# Tailsitter_sch.net
KiCad netlist of a schematic drawn in Altium Designer
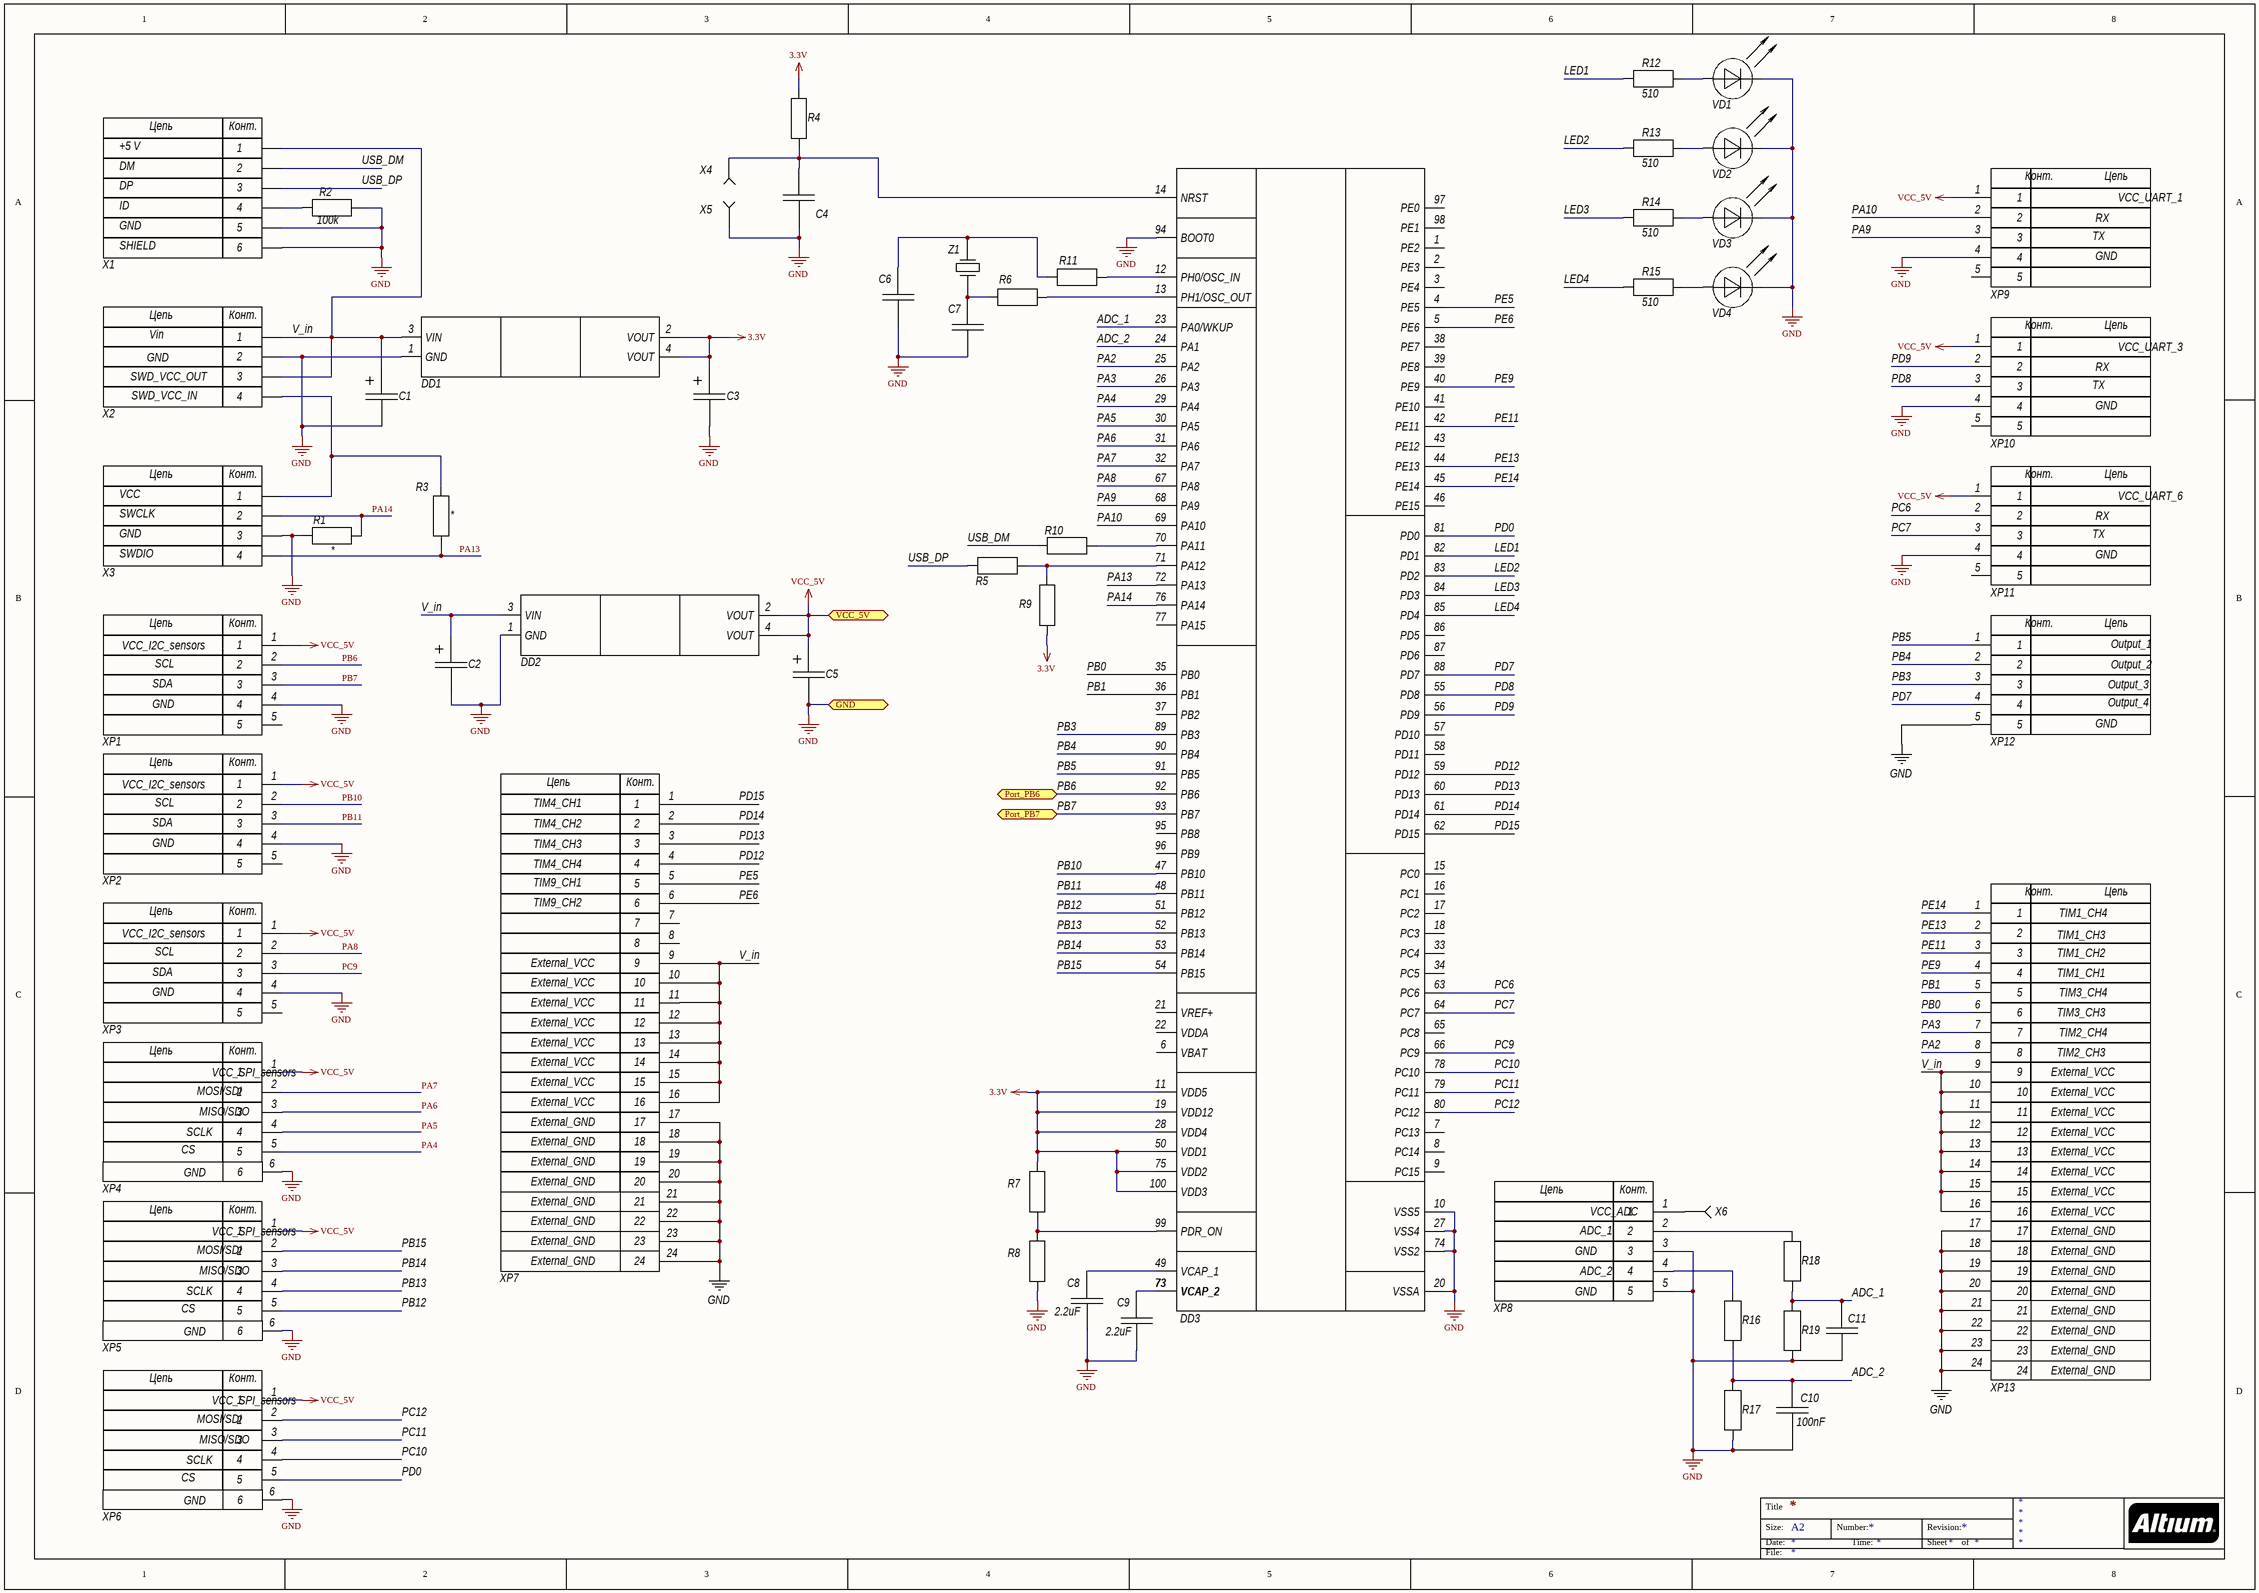
[diagram p0: Tailsitter_sch.SchDoc]

(export (version "E")
  (design (tool "Eeschema 10.0.6"))
  (components
    (comp (ref "C1")
      (value "Cap El Case A (Tantalum)")
      (footprint "CAP CASE A")
      (libsource (lib "Capacitors") (part "Cap El Case A (Tantalum)"))
    )
    (comp (ref "C2")
      (value "Cap El Case A (Tantalum)")
      (footprint "CAP CASE A")
      (libsource (lib "Capacitors") (part "Cap El Case A (Tantalum)"))
    )
    (comp (ref "C3")
      (value "Cap El Case A (Tantalum)")
      (footprint "CAP CASE A")
      (libsource (lib "Capacitors") (part "Cap El Case A (Tantalum)"))
    )
    (comp (ref "C4")
      (value "Cap EIA 0805")
      (footprint "CAP EIA 0805")
      (libsource (lib "Capacitors") (part "Cap EIA 0805"))
    )
    (comp (ref "C5")
      (value "Cap El Case A (Tantalum)")
      (footprint "CAP CASE A")
      (libsource (lib "Capacitors") (part "Cap El Case A (Tantalum)"))
    )
    (comp (ref "C6")
      (value "Cap EIA 0805")
      (footprint "CAP EIA 0805")
      (libsource (lib "Capacitors") (part "Cap EIA 0805"))
    )
    (comp (ref "C7")
      (value "Cap EIA 0805")
      (footprint "CAP EIA 0805")
      (libsource (lib "Capacitors") (part "Cap EIA 0805"))
    )
    (comp (ref "C8")
      (value "2.2uF")
      (footprint "CAP EIA 0805")
      (fields (field (name "Comment") "Cap EIA 0805"))
      (libsource (lib "Capacitors") (part "Cap EIA 0805"))
    )
    (comp (ref "C9")
      (value "2.2uF")
      (footprint "CAP EIA 0805")
      (fields (field (name "Comment") "Cap EIA 0805"))
      (libsource (lib "Capacitors") (part "Cap EIA 0805"))
    )
    (comp (ref "C10")
      (value "100nF")
      (footprint "CAP EIA 0805")
      (fields (field (name "Comment") "Cap EIA 0805"))
      (libsource (lib "Capacitors") (part "Cap EIA 0805"))
    )
    (comp (ref "C11")
      (value "Cap EIA 0805")
      (footprint "CAP EIA 0805")
      (libsource (lib "Capacitors") (part "Cap EIA 0805"))
    )
    (comp (ref "DD1")
      (value "LM1117S50")
      (footprint "SOT-223_M")
      (description "LDO Voltage Regulator")
      (fields (field (name "MANUFACTURER") "ST Microelectronics"))
      (libsource (lib "Integrated_Circuits") (part "LM1117S50"))
    )
    (comp (ref "DD2")
      (value "LM1117S50")
      (footprint "SOT-223_M")
      (description "LDO Voltage Regulator")
      (fields (field (name "MANUFACTURER") "ST Microelectronics"))
      (libsource (lib "Integrated_Circuits") (part "LM1117S50"))
    )
    (comp (ref "DD3")
      (value "STM32F407")
      (footprint "LQFP 14x14-100L")
      (description "ARM Cortex-M4 MCU with 1 Mbytes Flash, 168 MHz CPU")
      (fields (field (name "MANUFACTURER") "ST"))
      (libsource (lib "Integrated_Circuits") (part "STM32F407"))
    )
    (comp (ref "R1")
      (value "*")
      (footprint "RES EIA 0805")
      (fields (field (name "ALTIUM_VALUE") "*"))
      (libsource (lib "Resistors") (part "Res EIA 0805"))
    )
    (comp (ref "R2")
      (value "100k")
      (footprint "RES EIA 0805")
      (fields (field (name "Comment") "Res EIA 0805"))
      (libsource (lib "Resistors") (part "Res EIA 0805"))
    )
    (comp (ref "R3")
      (value "*")
      (footprint "RES EIA 0805")
      (fields (field (name "ALTIUM_VALUE") "*"))
      (libsource (lib "Resistors") (part "Res EIA 0805"))
    )
    (comp (ref "R4")
      (value "Res EIA 0805")
      (footprint "RES EIA 0805")
      (libsource (lib "Resistors") (part "Res EIA 0805"))
    )
    (comp (ref "R5")
      (value "Res EIA 0805")
      (footprint "RES EIA 0805")
      (libsource (lib "Resistors") (part "Res EIA 0805"))
    )
    (comp (ref "R6")
      (value "Res EIA 0805")
      (footprint "RES EIA 0805")
      (libsource (lib "Resistors") (part "Res EIA 0805"))
    )
    (comp (ref "R7")
      (value "Res EIA 0805")
      (footprint "RES EIA 0805")
      (libsource (lib "Resistors") (part "Res EIA 0805"))
    )
    (comp (ref "R8")
      (value "Res EIA 0805")
      (footprint "RES EIA 0805")
      (libsource (lib "Resistors") (part "Res EIA 0805"))
    )
    (comp (ref "R9")
      (value "Res EIA 0805")
      (footprint "RES EIA 0805")
      (libsource (lib "Resistors") (part "Res EIA 0805"))
    )
    (comp (ref "R10")
      (value "Res EIA 0805")
      (footprint "RES EIA 0805")
      (libsource (lib "Resistors") (part "Res EIA 0805"))
    )
    (comp (ref "R11")
      (value "Res EIA 0805")
      (footprint "RES EIA 0805")
      (libsource (lib "Resistors") (part "Res EIA 0805"))
    )
    (comp (ref "R12")
      (value "510")
      (footprint "RES EIA 0805")
      (fields (field (name "Comment") "Res EIA 0805"))
      (libsource (lib "Resistors") (part "Res EIA 0805"))
    )
    (comp (ref "R13")
      (value "510")
      (footprint "RES EIA 0805")
      (fields (field (name "Comment") "Res EIA 0805"))
      (libsource (lib "Resistors") (part "Res EIA 0805"))
    )
    (comp (ref "R14")
      (value "510")
      (footprint "RES EIA 0805")
      (fields (field (name "Comment") "Res EIA 0805"))
      (libsource (lib "Resistors") (part "Res EIA 0805"))
    )
    (comp (ref "R15")
      (value "510")
      (footprint "RES EIA 0805")
      (fields (field (name "Comment") "Res EIA 0805"))
      (libsource (lib "Resistors") (part "Res EIA 0805"))
    )
    (comp (ref "R16")
      (value "Res EIA 0805")
      (footprint "RES EIA 0805")
      (libsource (lib "Resistors") (part "Res EIA 0805"))
    )
    (comp (ref "R17")
      (value "Res EIA 0805")
      (footprint "RES EIA 0805")
      (libsource (lib "Resistors") (part "Res EIA 0805"))
    )
    (comp (ref "R18")
      (value "Res EIA 0805")
      (footprint "RES EIA 0805")
      (libsource (lib "Resistors") (part "Res EIA 0805"))
    )
    (comp (ref "R19")
      (value "Res EIA 0805")
      (footprint "RES EIA 0805")
      (libsource (lib "Resistors") (part "Res EIA 0805"))
    )
    (comp (ref "VD1")
      (value "KP-2012xxxx")
      (footprint "SMD LED 0805 (GREEN)")
      (description "SMD Led")
      (libsource (lib "Semiconductors") (part "FYLS-0805xxxx"))
    )
    (comp (ref "VD2")
      (value "KP-2012xxxx")
      (footprint "SMD LED 0805 (GREEN)")
      (description "SMD Led")
      (libsource (lib "Semiconductors") (part "FYLS-0805xxxx"))
    )
    (comp (ref "VD3")
      (value "KP-2012xxxx")
      (footprint "SMD LED 0805 (GREEN)")
      (description "SMD Led")
      (libsource (lib "Semiconductors") (part "FYLS-0805xxxx"))
    )
    (comp (ref "VD4")
      (value "KP-2012xxxx")
      (footprint "SMD LED 0805 (GREEN)")
      (description "SMD Led")
      (libsource (lib "Semiconductors") (part "FYLS-0805xxxx"))
    )
    (comp (ref "X1")
      (value "USB/M-1J")
      (footprint "USB/M-1J (DS1104)")
      (description "Mini USB Receptacle")
      (fields (field (name "MANUFACTURER") "Connfly"))
      (libsource (lib "Connectors") (part "USB/M-1J"))
    )
    (comp (ref "X2")
      (value "~")
      (footprint "SWD")
      (fields (field (name "MANUFACTURER") "Hsuan Mao(Китай)"))
      (libsource (lib "Connectors") (part "PLS-4"))
    )
    (comp (ref "X3")
      (value "~")
      (footprint "SWD")
      (fields (field (name "MANUFACTURER") "Тайвань(Китай)"))
      (libsource (lib "Connectors") (part "SWD(PLS- 4)"))
    )
    (comp (ref "X4")
      (value "Pin_Referal")
      (footprint "Pin - Referal")
      (description "Generic Pin Contact")
      (libsource (lib "Connectors") (part "Pin_Referal"))
    )
    (comp (ref "X5")
      (value "Pin_Referal")
      (footprint "Pin - Referal")
      (description "Generic Pin Contact")
      (libsource (lib "Connectors") (part "Pin_Referal"))
    )
    (comp (ref "X6")
      (value "Pin_Referal")
      (footprint "Pin - Referal")
      (description "Generic Pin Contact")
      (libsource (lib "Connectors") (part "Pin_Referal"))
    )
    (comp (ref "XP1")
      (value "BM05B-SRSS-TB")
      (footprint "BM05B-SRSS-TB")
      (description "5-Pin Angle Connector")
      (fields (field (name "MANUFACTURER") "JST"))
      (libsource (lib "Connectors") (part "BM05B-SRSS-TB"))
    )
    (comp (ref "XP2")
      (value "BM05B-SRSS-TB")
      (footprint "BM05B-SRSS-TB")
      (description "5-Pin Angle Connector")
      (fields (field (name "MANUFACTURER") "JST"))
      (libsource (lib "Connectors") (part "BM05B-SRSS-TB"))
    )
    (comp (ref "XP3")
      (value "BM05B-SRSS-TB")
      (footprint "BM05B-SRSS-TB")
      (description "5-Pin Angle Connector")
      (fields (field (name "MANUFACTURER") "JST"))
      (libsource (lib "Connectors") (part "BM05B-SRSS-TB"))
    )
    (comp (ref "XP4")
      (value "Micro JST 6 pin")
      (footprint "Micro JST-6 pin")
      (libsource (lib "Connectors") (part "Micro JST-6 pin"))
    )
    (comp (ref "XP5")
      (value "Micro JST 6 pin")
      (footprint "Micro JST-6 pin")
      (libsource (lib "Connectors") (part "Micro JST-6 pin"))
    )
    (comp (ref "XP6")
      (value "Micro JST 6 pin")
      (footprint "Micro JST-6 pin")
      (libsource (lib "Connectors") (part "Micro JST-6 pin"))
    )
    (comp (ref "XP7")
      (value "PLD-24-3")
      (footprint "PLD-24-3")
      (description "Разъем для подключение RC-приемника или регуляторов хода")
      (libsource (lib "Connectors") (part "PLD-24-3"))
    )
    (comp (ref "XP8")
      (value "BM05B-SRSS-TB")
      (footprint "BM05B-SRSS-TB")
      (description "5-Pin Angle Connector")
      (fields (field (name "MANUFACTURER") "JST"))
      (libsource (lib "Connectors") (part "BM05B-SRSS-TB"))
    )
    (comp (ref "XP9")
      (value "BM05B-SRSS-TB")
      (footprint "BM05B-SRSS-TB")
      (description "5-Pin Angle Connector")
      (fields (field (name "MANUFACTURER") "JST"))
      (libsource (lib "Connectors") (part "BM05B-SRSS-TB"))
    )
    (comp (ref "XP10")
      (value "BM05B-SRSS-TB")
      (footprint "BM05B-SRSS-TB")
      (description "5-Pin Angle Connector")
      (fields (field (name "MANUFACTURER") "JST"))
      (libsource (lib "Connectors") (part "BM05B-SRSS-TB"))
    )
    (comp (ref "XP11")
      (value "BM05B-SRSS-TB")
      (footprint "BM05B-SRSS-TB")
      (description "5-Pin Angle Connector")
      (fields (field (name "MANUFACTURER") "JST"))
      (libsource (lib "Connectors") (part "BM05B-SRSS-TB"))
    )
    (comp (ref "XP12")
      (value "BM05B-SRSS-TB")
      (footprint "BM05B-SRSS-TB")
      (description "5-Pin Angle Connector")
      (fields (field (name "MANUFACTURER") "JST"))
      (libsource (lib "Connectors") (part "BM05B-SRSS-TB"))
    )
    (comp (ref "XP13")
      (value "PLD-24-3")
      (footprint "PLD-24-3")
      (description "Разъем для подключение RC-приемника или регуляторов хода")
      (libsource (lib "Connectors") (part "PLD-24-3"))
    )
    (comp (ref "Z1")
      (value "ABM3-8.000MHZ-D2Y-T")
      (footprint "bq smd 5x3.2")
      (fields (field (name "MANUFACTURER") "ABRACON"))
      (libsource (lib "Converters") (part "ABM3-8.000MHZ-D2Y-T"))
    )
  )
  (nets
    (net (code "1") (name "/ADC_1") (class "Default")
      (node (ref "C11") (pin "1") (pinfunction "1_1") (pintype "passive"))
      (node (ref "DD3") (pin "23") (pinfunction "PA0/WKUP_23") (pintype "passive"))
      (node (ref "R18") (pin "1") (pinfunction "1_1") (pintype "passive"))
      (node (ref "R19") (pin "2") (pinfunction "2_2") (pintype "passive"))
    )
    (net (code "2") (name "/ADC_2") (class "Default")
      (node (ref "C10") (pin "1") (pinfunction "1_1") (pintype "passive"))
      (node (ref "DD3") (pin "24") (pinfunction "PA1_24") (pintype "passive"))
      (node (ref "R16") (pin "1") (pinfunction "1_1") (pintype "passive"))
      (node (ref "R17") (pin "2") (pinfunction "2_2") (pintype "passive"))
    )
    (net (code "3") (name "/LED1") (class "Default")
      (node (ref "DD3") (pin "82") (pinfunction "PD1_82") (pintype "passive"))
      (node (ref "R12") (pin "1") (pinfunction "1_1") (pintype "passive"))
    )
    (net (code "4") (name "/LED2") (class "Default")
      (node (ref "DD3") (pin "83") (pinfunction "PD2_83") (pintype "passive"))
      (node (ref "R13") (pin "1") (pinfunction "1_1") (pintype "passive"))
    )
    (net (code "5") (name "/LED3") (class "Default")
      (node (ref "DD3") (pin "84") (pinfunction "PD3_84") (pintype "passive"))
      (node (ref "R14") (pin "1") (pinfunction "1_1") (pintype "passive"))
    )
    (net (code "6") (name "/LED4") (class "Default")
      (node (ref "DD3") (pin "85") (pinfunction "PD4_85") (pintype "passive"))
      (node (ref "R15") (pin "1") (pinfunction "1_1") (pintype "passive"))
    )
    (net (code "7") (name "/PA2") (class "Default")
      (node (ref "DD3") (pin "25") (pinfunction "PA2_25") (pintype "passive"))
      (node (ref "XP13") (pin "8") (pinfunction "8_8") (pintype "passive"))
    )
    (net (code "8") (name "/PA3") (class "Default")
      (node (ref "DD3") (pin "26") (pinfunction "PA3_26") (pintype "passive"))
      (node (ref "XP13") (pin "7") (pinfunction "7_7") (pintype "passive"))
    )
    (net (code "9") (name "/PA4") (class "Default")
      (node (ref "DD3") (pin "29") (pinfunction "PA4_29") (pintype "passive"))
      (node (ref "XP4") (pin "5") (pinfunction "5_5") (pintype "passive"))
    )
    (net (code "10") (name "/PA5") (class "Default")
      (node (ref "DD3") (pin "30") (pinfunction "PA5_30") (pintype "passive"))
      (node (ref "XP4") (pin "4") (pinfunction "4_4") (pintype "passive"))
    )
    (net (code "11") (name "/PA6") (class "Default")
      (node (ref "DD3") (pin "31") (pinfunction "PA6_31") (pintype "passive"))
      (node (ref "XP4") (pin "3") (pinfunction "3_3") (pintype "passive"))
    )
    (net (code "12") (name "/PA7") (class "Default")
      (node (ref "DD3") (pin "32") (pinfunction "PA7_32") (pintype "passive"))
      (node (ref "XP4") (pin "2") (pinfunction "2_2") (pintype "passive"))
    )
    (net (code "13") (name "/PA8") (class "Default")
      (node (ref "DD3") (pin "67") (pinfunction "PA8_67") (pintype "passive"))
      (node (ref "XP3") (pin "2") (pinfunction "2_2") (pintype "passive"))
    )
    (net (code "14") (name "/PA9") (class "Default")
      (node (ref "DD3") (pin "68") (pinfunction "PA9_68") (pintype "passive"))
      (node (ref "XP9") (pin "3") (pinfunction "3_3") (pintype "passive"))
    )
    (net (code "15") (name "/PA10") (class "Default")
      (node (ref "DD3") (pin "69") (pinfunction "PA10_69") (pintype "passive"))
      (node (ref "XP9") (pin "2") (pinfunction "2_2") (pintype "passive"))
    )
    (net (code "16") (name "/PA13") (class "Default")
      (node (ref "DD3") (pin "72") (pinfunction "PA13_72") (pintype "passive"))
      (node (ref "R3") (pin "2") (pinfunction "2_2") (pintype "passive"))
      (node (ref "X3") (pin "4") (pinfunction "SWDIO_4") (pintype "passive"))
    )
    (net (code "17") (name "/PA14") (class "Default")
      (node (ref "DD3") (pin "76") (pinfunction "PA14_76") (pintype "passive"))
      (node (ref "R1") (pin "1") (pinfunction "1_1") (pintype "passive"))
      (node (ref "X3") (pin "2") (pinfunction "SWCLK_2") (pintype "passive"))
    )
    (net (code "18") (name "/PB0") (class "Default")
      (node (ref "DD3") (pin "35") (pinfunction "PB0_35") (pintype "passive"))
      (node (ref "XP13") (pin "6") (pinfunction "6_6") (pintype "passive"))
    )
    (net (code "19") (name "/PB1") (class "Default")
      (node (ref "DD3") (pin "36") (pinfunction "PB1_36") (pintype "passive"))
      (node (ref "XP13") (pin "5") (pinfunction "5_5") (pintype "passive"))
    )
    (net (code "20") (name "/PB3") (class "Default")
      (node (ref "DD3") (pin "89") (pinfunction "PB3_89") (pintype "passive"))
      (node (ref "XP12") (pin "3") (pinfunction "3_3") (pintype "passive"))
    )
    (net (code "21") (name "/PB4") (class "Default")
      (node (ref "DD3") (pin "90") (pinfunction "PB4_90") (pintype "passive"))
      (node (ref "XP12") (pin "2") (pinfunction "2_2") (pintype "passive"))
    )
    (net (code "22") (name "/PB5") (class "Default")
      (node (ref "DD3") (pin "91") (pinfunction "PB5_91") (pintype "passive"))
      (node (ref "XP12") (pin "1") (pinfunction "1_1") (pintype "passive"))
    )
    (net (code "23") (name "/PB6") (class "Default")
      (node (ref "DD3") (pin "92") (pinfunction "PB6_92") (pintype "passive"))
      (node (ref "XP1") (pin "2") (pinfunction "2_2") (pintype "passive"))
    )
    (net (code "24") (name "/PB7") (class "Default")
      (node (ref "DD3") (pin "93") (pinfunction "PB7_93") (pintype "passive"))
      (node (ref "XP1") (pin "3") (pinfunction "3_3") (pintype "passive"))
    )
    (net (code "25") (name "/PB10") (class "Default")
      (node (ref "DD3") (pin "47") (pinfunction "PB10_47") (pintype "passive"))
      (node (ref "XP2") (pin "2") (pinfunction "2_2") (pintype "passive"))
    )
    (net (code "26") (name "/PB11") (class "Default")
      (node (ref "DD3") (pin "48") (pinfunction "PB11_48") (pintype "passive"))
      (node (ref "XP2") (pin "3") (pinfunction "3_3") (pintype "passive"))
    )
    (net (code "27") (name "/PB12") (class "Default")
      (node (ref "DD3") (pin "51") (pinfunction "PB12_51") (pintype "passive"))
      (node (ref "XP5") (pin "5") (pinfunction "5_5") (pintype "passive"))
    )
    (net (code "28") (name "/PB13") (class "Default")
      (node (ref "DD3") (pin "52") (pinfunction "PB13_52") (pintype "passive"))
      (node (ref "XP5") (pin "4") (pinfunction "4_4") (pintype "passive"))
    )
    (net (code "29") (name "/PB14") (class "Default")
      (node (ref "DD3") (pin "53") (pinfunction "PB14_53") (pintype "passive"))
      (node (ref "XP5") (pin "3") (pinfunction "3_3") (pintype "passive"))
    )
    (net (code "30") (name "/PB15") (class "Default")
      (node (ref "DD3") (pin "54") (pinfunction "PB15_54") (pintype "passive"))
      (node (ref "XP5") (pin "2") (pinfunction "2_2") (pintype "passive"))
    )
    (net (code "31") (name "/PC6") (class "Default")
      (node (ref "DD3") (pin "63") (pinfunction "PC6_63") (pintype "passive"))
      (node (ref "XP11") (pin "2") (pinfunction "2_2") (pintype "passive"))
    )
    (net (code "32") (name "/PC7") (class "Default")
      (node (ref "DD3") (pin "64") (pinfunction "PC7_64") (pintype "passive"))
      (node (ref "XP11") (pin "3") (pinfunction "3_3") (pintype "passive"))
    )
    (net (code "33") (name "/PC9") (class "Default")
      (node (ref "DD3") (pin "66") (pinfunction "PC9_66") (pintype "passive"))
      (node (ref "XP3") (pin "3") (pinfunction "3_3") (pintype "passive"))
    )
    (net (code "34") (name "/PC10") (class "Default")
      (node (ref "DD3") (pin "78") (pinfunction "PC10_78") (pintype "passive"))
      (node (ref "XP6") (pin "4") (pinfunction "4_4") (pintype "passive"))
    )
    (net (code "35") (name "/PC11") (class "Default")
      (node (ref "DD3") (pin "79") (pinfunction "PC11_79") (pintype "passive"))
      (node (ref "XP6") (pin "3") (pinfunction "3_3") (pintype "passive"))
    )
    (net (code "36") (name "/PC12") (class "Default")
      (node (ref "DD3") (pin "80") (pinfunction "PC12_80") (pintype "passive"))
      (node (ref "XP6") (pin "2") (pinfunction "2_2") (pintype "passive"))
    )
    (net (code "37") (name "/PD0") (class "Default")
      (node (ref "DD3") (pin "81") (pinfunction "PD0_81") (pintype "passive"))
      (node (ref "XP6") (pin "5") (pinfunction "5_5") (pintype "passive"))
    )
    (net (code "38") (name "/PD7") (class "Default")
      (node (ref "DD3") (pin "88") (pinfunction "PD7_88") (pintype "passive"))
      (node (ref "XP12") (pin "4") (pinfunction "4_4") (pintype "passive"))
    )
    (net (code "39") (name "/PD8") (class "Default")
      (node (ref "DD3") (pin "55") (pinfunction "PD8_55") (pintype "passive"))
      (node (ref "XP10") (pin "3") (pinfunction "3_3") (pintype "passive"))
    )
    (net (code "40") (name "/PD9") (class "Default")
      (node (ref "DD3") (pin "56") (pinfunction "PD9_56") (pintype "passive"))
      (node (ref "XP10") (pin "2") (pinfunction "2_2") (pintype "passive"))
    )
    (net (code "41") (name "/PD12") (class "Default")
      (node (ref "DD3") (pin "59") (pinfunction "PD12_59") (pintype "passive"))
      (node (ref "XP7") (pin "4") (pinfunction "4_4") (pintype "passive"))
    )
    (net (code "42") (name "/PD13") (class "Default")
      (node (ref "DD3") (pin "60") (pinfunction "PD13_60") (pintype "passive"))
      (node (ref "XP7") (pin "3") (pinfunction "3_3") (pintype "passive"))
    )
    (net (code "43") (name "/PD14") (class "Default")
      (node (ref "DD3") (pin "61") (pinfunction "PD14_61") (pintype "passive"))
      (node (ref "XP7") (pin "2") (pinfunction "2_2") (pintype "passive"))
    )
    (net (code "44") (name "/PD15") (class "Default")
      (node (ref "DD3") (pin "62") (pinfunction "PD15_62") (pintype "passive"))
      (node (ref "XP7") (pin "1") (pinfunction "1_1") (pintype "passive"))
    )
    (net (code "45") (name "/PE5") (class "Default")
      (node (ref "DD3") (pin "4") (pinfunction "PE5_4") (pintype "passive"))
      (node (ref "XP7") (pin "5") (pinfunction "5_5") (pintype "passive"))
    )
    (net (code "46") (name "/PE6") (class "Default")
      (node (ref "DD3") (pin "5") (pinfunction "PE6_5") (pintype "passive"))
      (node (ref "XP7") (pin "6") (pinfunction "6_6") (pintype "passive"))
    )
    (net (code "47") (name "/PE9") (class "Default")
      (node (ref "DD3") (pin "40") (pinfunction "PE9_40") (pintype "passive"))
      (node (ref "XP13") (pin "4") (pinfunction "4_4") (pintype "passive"))
    )
    (net (code "48") (name "/PE11") (class "Default")
      (node (ref "DD3") (pin "42") (pinfunction "PE11_42") (pintype "passive"))
      (node (ref "XP13") (pin "3") (pinfunction "3_3") (pintype "passive"))
    )
    (net (code "49") (name "/PE13") (class "Default")
      (node (ref "DD3") (pin "44") (pinfunction "PE13_44") (pintype "passive"))
      (node (ref "XP13") (pin "2") (pinfunction "2_2") (pintype "passive"))
    )
    (net (code "50") (name "/PE14") (class "Default")
      (node (ref "DD3") (pin "45") (pinfunction "PE14_45") (pintype "passive"))
      (node (ref "XP13") (pin "1") (pinfunction "1_1") (pintype "passive"))
    )
    (net (code "51") (name "/USB_DM") (class "Default")
      (node (ref "R10") (pin "1") (pinfunction "1_1") (pintype "passive"))
      (node (ref "X1") (pin "2") (pinfunction "DM_2") (pintype "passive"))
    )
    (net (code "52") (name "/USB_DP") (class "Default")
      (node (ref "R5") (pin "1") (pinfunction "1_1") (pintype "passive"))
      (node (ref "X1") (pin "3") (pinfunction "DP_3") (pintype "passive"))
    )
    (net (code "53") (name "/V_in") (class "Default")
      (node (ref "C1") (pin "1") (pinfunction "1_1") (pintype "passive"))
      (node (ref "C2") (pin "1") (pinfunction "1_1") (pintype "passive"))
      (node (ref "DD1") (pin "3") (pinfunction "VIN_3") (pintype "passive"))
      (node (ref "DD2") (pin "3") (pinfunction "VIN_3") (pintype "passive"))
      (node (ref "X1") (pin "1") (pinfunction "+5_V_1") (pintype "passive"))
      (node (ref "X2") (pin "1") (pinfunction "1_1") (pintype "passive"))
      (node (ref "X2") (pin "3") (pinfunction "3_3") (pintype "passive"))
      (node (ref "XP13") (pin "10") (pinfunction "10_10") (pintype "passive"))
      (node (ref "XP13") (pin "11") (pinfunction "11_11") (pintype "passive"))
      (node (ref "XP13") (pin "12") (pinfunction "12_12") (pintype "passive"))
      (node (ref "XP13") (pin "13") (pinfunction "13_13") (pintype "passive"))
      (node (ref "XP13") (pin "14") (pinfunction "14_14") (pintype "passive"))
      (node (ref "XP13") (pin "15") (pinfunction "15_15") (pintype "passive"))
      (node (ref "XP13") (pin "16") (pinfunction "16_16") (pintype "passive"))
      (node (ref "XP13") (pin "9") (pinfunction "9_9") (pintype "passive"))
      (node (ref "XP7") (pin "10") (pinfunction "10_10") (pintype "passive"))
      (node (ref "XP7") (pin "11") (pinfunction "11_11") (pintype "passive"))
      (node (ref "XP7") (pin "12") (pinfunction "12_12") (pintype "passive"))
      (node (ref "XP7") (pin "13") (pinfunction "13_13") (pintype "passive"))
      (node (ref "XP7") (pin "14") (pinfunction "14_14") (pintype "passive"))
      (node (ref "XP7") (pin "15") (pinfunction "15_15") (pintype "passive"))
      (node (ref "XP7") (pin "16") (pinfunction "16_16") (pintype "passive"))
      (node (ref "XP7") (pin "9") (pinfunction "9_9") (pintype "passive"))
    )
    (net (code "54") (name "3.3V") (class "Default")
      (node (ref "C3") (pin "1") (pinfunction "1_1") (pintype "passive"))
      (node (ref "DD1") (pin "2") (pinfunction "VOUT_2") (pintype "passive"))
      (node (ref "DD1") (pin "4") (pinfunction "VOUT_4") (pintype "passive"))
      (node (ref "DD3") (pin "100") (pinfunction "VDD3_100") (pintype "passive"))
      (node (ref "DD3") (pin "11") (pinfunction "VDD5_11") (pintype "passive"))
      (node (ref "DD3") (pin "19") (pinfunction "VDD12_19") (pintype "passive"))
      (node (ref "DD3") (pin "28") (pinfunction "VDD4_28") (pintype "passive"))
      (node (ref "DD3") (pin "50") (pinfunction "VDD1_50") (pintype "passive"))
      (node (ref "DD3") (pin "75") (pinfunction "VDD2_75") (pintype "passive"))
      (node (ref "R4") (pin "2") (pinfunction "2_2") (pintype "passive"))
      (node (ref "R7") (pin "2") (pinfunction "2_2") (pintype "passive"))
      (node (ref "R9") (pin "1") (pinfunction "1_1") (pintype "passive"))
    )
    (net (code "55") (name "GND") (class "Default")
      (node (ref "C1") (pin "2") (pinfunction "2_2") (pintype "passive"))
      (node (ref "C10") (pin "2") (pinfunction "2_2") (pintype "passive"))
      (node (ref "C11") (pin "2") (pinfunction "2_2") (pintype "passive"))
      (node (ref "C2") (pin "2") (pinfunction "2_2") (pintype "passive"))
      (node (ref "C3") (pin "2") (pinfunction "2_2") (pintype "passive"))
      (node (ref "C4") (pin "1") (pinfunction "1_1") (pintype "passive"))
      (node (ref "C5") (pin "2") (pinfunction "2_2") (pintype "passive"))
      (node (ref "C6") (pin "2") (pinfunction "2_2") (pintype "passive"))
      (node (ref "C7") (pin "2") (pinfunction "2_2") (pintype "passive"))
      (node (ref "C8") (pin "1") (pinfunction "1_1") (pintype "passive"))
      (node (ref "C9") (pin "1") (pinfunction "1_1") (pintype "passive"))
      (node (ref "DD1") (pin "1") (pinfunction "GND_1") (pintype "passive"))
      (node (ref "DD2") (pin "1") (pinfunction "GND_1") (pintype "passive"))
      (node (ref "DD3") (pin "10") (pinfunction "VSS5_10") (pintype "passive"))
      (node (ref "DD3") (pin "20") (pinfunction "VSSA_20") (pintype "passive"))
      (node (ref "DD3") (pin "27") (pinfunction "VSS4_27") (pintype "passive"))
      (node (ref "DD3") (pin "74") (pinfunction "VSS2_74") (pintype "passive"))
      (node (ref "DD3") (pin "94") (pinfunction "BOOT0_94") (pintype "passive"))
      (node (ref "R1") (pin "2") (pinfunction "2_2") (pintype "passive"))
      (node (ref "R17") (pin "1") (pinfunction "1_1") (pintype "passive"))
      (node (ref "R19") (pin "1") (pinfunction "1_1") (pintype "passive"))
      (node (ref "R2") (pin "2") (pinfunction "2_2") (pintype "passive"))
      (node (ref "R8") (pin "2") (pinfunction "2_2") (pintype "passive"))
      (node (ref "VD1") (pin "2") (pinfunction "K_2") (pintype "passive"))
      (node (ref "VD2") (pin "2") (pinfunction "K_2") (pintype "passive"))
      (node (ref "VD3") (pin "2") (pinfunction "K_2") (pintype "passive"))
      (node (ref "VD4") (pin "2") (pinfunction "K_2") (pintype "passive"))
      (node (ref "X1") (pin "5") (pinfunction "GND_5") (pintype "passive"))
      (node (ref "X2") (pin "2") (pinfunction "2_2") (pintype "passive"))
      (node (ref "X3") (pin "3") (pinfunction "GND_3") (pintype "passive"))
      (node (ref "X5") (pin "1") (pinfunction "1_1") (pintype "passive"))
      (node (ref "XP1") (pin "4") (pinfunction "4_4") (pintype "passive"))
      (node (ref "XP10") (pin "4") (pinfunction "4_4") (pintype "passive"))
      (node (ref "XP11") (pin "4") (pinfunction "4_4") (pintype "passive"))
      (node (ref "XP12") (pin "5") (pinfunction "5_5") (pintype "passive"))
      (node (ref "XP13") (pin "17") (pinfunction "17_17") (pintype "passive"))
      (node (ref "XP13") (pin "18") (pinfunction "18_18") (pintype "passive"))
      (node (ref "XP13") (pin "19") (pinfunction "19_19") (pintype "passive"))
      (node (ref "XP13") (pin "20") (pinfunction "20_20") (pintype "passive"))
      (node (ref "XP13") (pin "21") (pinfunction "21_21") (pintype "passive"))
      (node (ref "XP13") (pin "22") (pinfunction "22_22") (pintype "passive"))
      (node (ref "XP13") (pin "23") (pinfunction "23_23") (pintype "passive"))
      (node (ref "XP13") (pin "24") (pinfunction "24_24") (pintype "passive"))
      (node (ref "XP2") (pin "4") (pinfunction "4_4") (pintype "passive"))
      (node (ref "XP3") (pin "4") (pinfunction "4_4") (pintype "passive"))
      (node (ref "XP4") (pin "6") (pinfunction "6_6") (pintype "passive"))
      (node (ref "XP5") (pin "6") (pinfunction "6_6") (pintype "passive"))
      (node (ref "XP6") (pin "6") (pinfunction "6_6") (pintype "passive"))
      (node (ref "XP7") (pin "17") (pinfunction "17_17") (pintype "passive"))
      (node (ref "XP7") (pin "18") (pinfunction "18_18") (pintype "passive"))
      (node (ref "XP7") (pin "19") (pinfunction "19_19") (pintype "passive"))
      (node (ref "XP7") (pin "20") (pinfunction "20_20") (pintype "passive"))
      (node (ref "XP7") (pin "21") (pinfunction "21_21") (pintype "passive"))
      (node (ref "XP7") (pin "22") (pinfunction "22_22") (pintype "passive"))
      (node (ref "XP7") (pin "23") (pinfunction "23_23") (pintype "passive"))
      (node (ref "XP7") (pin "24") (pinfunction "24_24") (pintype "passive"))
      (node (ref "XP8") (pin "3") (pinfunction "3_3") (pintype "passive"))
      (node (ref "XP8") (pin "5") (pinfunction "5_5") (pintype "passive"))
      (node (ref "XP9") (pin "4") (pinfunction "4_4") (pintype "passive"))
    )
    (net (code "56") (name "Net-(C6-Pad1)") (class "Default")
      (node (ref "C6") (pin "1") (pinfunction "1_1") (pintype "passive"))
      (node (ref "R11") (pin "1") (pinfunction "1_1") (pintype "passive"))
      (node (ref "Z1") (pin "1") (pinfunction "1_1") (pintype "passive"))
    )
    (net (code "57") (name "Net-(C7-Pad1)") (class "Default")
      (node (ref "C7") (pin "1") (pinfunction "1_1") (pintype "passive"))
      (node (ref "R6") (pin "1") (pinfunction "1_1") (pintype "passive"))
      (node (ref "Z1") (pin "2") (pinfunction "2_2") (pintype "passive"))
    )
    (net (code "58") (name "Net-(DD3-NRST)") (class "Default")
      (node (ref "C4") (pin "2") (pinfunction "2_2") (pintype "passive"))
      (node (ref "DD3") (pin "14") (pinfunction "NRST_14") (pintype "passive"))
      (node (ref "R4") (pin "1") (pinfunction "1_1") (pintype "passive"))
      (node (ref "X4") (pin "1") (pinfunction "1_1") (pintype "passive"))
    )
    (net (code "59") (name "Net-(DD3-PA11)") (class "Default")
      (node (ref "DD3") (pin "70") (pinfunction "PA11_70") (pintype "passive"))
      (node (ref "R10") (pin "2") (pinfunction "2_2") (pintype "passive"))
    )
    (net (code "60") (name "Net-(DD3-PA12)") (class "Default")
      (node (ref "DD3") (pin "71") (pinfunction "PA12_71") (pintype "passive"))
      (node (ref "R5") (pin "2") (pinfunction "2_2") (pintype "passive"))
      (node (ref "R9") (pin "2") (pinfunction "2_2") (pintype "passive"))
    )
    (net (code "61") (name "Net-(DD3-PDR_ON)") (class "Default")
      (node (ref "DD3") (pin "99") (pinfunction "PDR_ON_99") (pintype "passive"))
      (node (ref "R7") (pin "1") (pinfunction "1_1") (pintype "passive"))
      (node (ref "R8") (pin "1") (pinfunction "1_1") (pintype "passive"))
    )
    (net (code "62") (name "Net-(DD3-PH0{slash}OSC_IN)") (class "Default")
      (node (ref "DD3") (pin "12") (pinfunction "PH0/OSC_IN_12") (pintype "passive"))
      (node (ref "R11") (pin "2") (pinfunction "2_2") (pintype "passive"))
    )
    (net (code "63") (name "Net-(DD3-PH1{slash}OSC_OUT)") (class "Default")
      (node (ref "DD3") (pin "13") (pinfunction "PH1/OSC_OUT_13") (pintype "passive"))
      (node (ref "R6") (pin "2") (pinfunction "2_2") (pintype "passive"))
    )
    (net (code "64") (name "Net-(DD3-VCAP_1)") (class "Default")
      (node (ref "C8") (pin "2") (pinfunction "2_2") (pintype "passive"))
      (node (ref "DD3") (pin "49") (pinfunction "VCAP_1_49") (pintype "passive"))
    )
    (net (code "65") (name "Net-(DD3-VCAP_2)") (class "Default")
      (node (ref "C9") (pin "2") (pinfunction "2_2") (pintype "passive"))
      (node (ref "DD3") (pin "73") (pinfunction "VCAP_2_73") (pintype "passive"))
    )
    (net (code "66") (name "Net-(R16-Pad2)") (class "Default")
      (node (ref "R16") (pin "2") (pinfunction "2_2") (pintype "passive"))
      (node (ref "XP8") (pin "4") (pinfunction "4_4") (pintype "passive"))
    )
    (net (code "67") (name "Net-(R18-Pad2)") (class "Default")
      (node (ref "R18") (pin "2") (pinfunction "2_2") (pintype "passive"))
      (node (ref "XP8") (pin "2") (pinfunction "2_2") (pintype "passive"))
    )
    (net (code "68") (name "Net-(VD1-A)") (class "Default")
      (node (ref "R12") (pin "2") (pinfunction "2_2") (pintype "passive"))
      (node (ref "VD1") (pin "1") (pinfunction "A_1") (pintype "passive"))
    )
    (net (code "69") (name "Net-(VD2-A)") (class "Default")
      (node (ref "R13") (pin "2") (pinfunction "2_2") (pintype "passive"))
      (node (ref "VD2") (pin "1") (pinfunction "A_1") (pintype "passive"))
    )
    (net (code "70") (name "Net-(VD3-A)") (class "Default")
      (node (ref "R14") (pin "2") (pinfunction "2_2") (pintype "passive"))
      (node (ref "VD3") (pin "1") (pinfunction "A_1") (pintype "passive"))
    )
    (net (code "71") (name "Net-(VD4-A)") (class "Default")
      (node (ref "R15") (pin "2") (pinfunction "2_2") (pintype "passive"))
      (node (ref "VD4") (pin "1") (pinfunction "A_1") (pintype "passive"))
    )
    (net (code "72") (name "Net-(X1-ID)") (class "Default")
      (node (ref "R2") (pin "1") (pinfunction "1_1") (pintype "passive"))
      (node (ref "X1") (pin "4") (pinfunction "ID_4") (pintype "passive"))
    )
    (net (code "73") (name "Net-(X3-VCC)") (class "Default")
      (node (ref "R3") (pin "1") (pinfunction "1_1") (pintype "passive"))
      (node (ref "X2") (pin "4") (pinfunction "4_4") (pintype "passive"))
      (node (ref "X3") (pin "1") (pinfunction "VCC_1") (pintype "passive"))
    )
    (net (code "74") (name "Net-(X6-Pad1)") (class "Default")
      (node (ref "X6") (pin "1") (pinfunction "1_1") (pintype "passive"))
      (node (ref "XP8") (pin "1") (pinfunction "1_1") (pintype "passive"))
    )
    (net (code "75") (name "VCC_5V") (class "Default")
      (node (ref "C5") (pin "1") (pinfunction "1_1") (pintype "passive"))
      (node (ref "DD2") (pin "2") (pinfunction "VOUT_2") (pintype "passive"))
      (node (ref "DD2") (pin "4") (pinfunction "VOUT_4") (pintype "passive"))
      (node (ref "XP1") (pin "1") (pinfunction "1_1") (pintype "passive"))
      (node (ref "XP10") (pin "1") (pinfunction "1_1") (pintype "passive"))
      (node (ref "XP11") (pin "1") (pinfunction "1_1") (pintype "passive"))
      (node (ref "XP2") (pin "1") (pinfunction "1_1") (pintype "passive"))
      (node (ref "XP3") (pin "1") (pinfunction "1_1") (pintype "passive"))
      (node (ref "XP4") (pin "1") (pinfunction "1_1") (pintype "passive"))
      (node (ref "XP5") (pin "1") (pinfunction "1_1") (pintype "passive"))
      (node (ref "XP6") (pin "1") (pinfunction "1_1") (pintype "passive"))
      (node (ref "XP9") (pin "1") (pinfunction "1_1") (pintype "passive"))
    )
    (net (code "76") (name "unconnected-(DD3-PA15-Pad77)") (class "Default")
      (node (ref "DD3") (pin "77") (pinfunction "PA15_77") (pintype "passive"))
    )
    (net (code "77") (name "unconnected-(DD3-PB2-Pad37)") (class "Default")
      (node (ref "DD3") (pin "37") (pinfunction "PB2_37") (pintype "passive"))
    )
    (net (code "78") (name "unconnected-(DD3-PB8-Pad95)") (class "Default")
      (node (ref "DD3") (pin "95") (pinfunction "PB8_95") (pintype "passive"))
    )
    (net (code "79") (name "unconnected-(DD3-PB9-Pad96)") (class "Default")
      (node (ref "DD3") (pin "96") (pinfunction "PB9_96") (pintype "passive"))
    )
    (net (code "80") (name "unconnected-(DD3-PC0-Pad15)") (class "Default")
      (node (ref "DD3") (pin "15") (pinfunction "PC0_15") (pintype "passive"))
    )
    (net (code "81") (name "unconnected-(DD3-PC1-Pad16)") (class "Default")
      (node (ref "DD3") (pin "16") (pinfunction "PC1_16") (pintype "passive"))
    )
    (net (code "82") (name "unconnected-(DD3-PC2-Pad17)") (class "Default")
      (node (ref "DD3") (pin "17") (pinfunction "PC2_17") (pintype "passive"))
    )
    (net (code "83") (name "unconnected-(DD3-PC3-Pad18)") (class "Default")
      (node (ref "DD3") (pin "18") (pinfunction "PC3_18") (pintype "passive"))
    )
    (net (code "84") (name "unconnected-(DD3-PC4-Pad33)") (class "Default")
      (node (ref "DD3") (pin "33") (pinfunction "PC4_33") (pintype "passive"))
    )
    (net (code "85") (name "unconnected-(DD3-PC5-Pad34)") (class "Default")
      (node (ref "DD3") (pin "34") (pinfunction "PC5_34") (pintype "passive"))
    )
    (net (code "86") (name "unconnected-(DD3-PC8-Pad65)") (class "Default")
      (node (ref "DD3") (pin "65") (pinfunction "PC8_65") (pintype "passive"))
    )
    (net (code "87") (name "unconnected-(DD3-PC13-Pad7)") (class "Default")
      (node (ref "DD3") (pin "7") (pinfunction "PC13_7") (pintype "passive"))
    )
    (net (code "88") (name "unconnected-(DD3-PC14-Pad8)") (class "Default")
      (node (ref "DD3") (pin "8") (pinfunction "PC14_8") (pintype "passive"))
    )
    (net (code "89") (name "unconnected-(DD3-PC15-Pad9)") (class "Default")
      (node (ref "DD3") (pin "9") (pinfunction "PC15_9") (pintype "passive"))
    )
    (net (code "90") (name "unconnected-(DD3-PD5-Pad86)") (class "Default")
      (node (ref "DD3") (pin "86") (pinfunction "PD5_86") (pintype "passive"))
    )
    (net (code "91") (name "unconnected-(DD3-PD6-Pad87)") (class "Default")
      (node (ref "DD3") (pin "87") (pinfunction "PD6_87") (pintype "passive"))
    )
    (net (code "92") (name "unconnected-(DD3-PD10-Pad57)") (class "Default")
      (node (ref "DD3") (pin "57") (pinfunction "PD10_57") (pintype "passive"))
    )
    (net (code "93") (name "unconnected-(DD3-PD11-Pad58)") (class "Default")
      (node (ref "DD3") (pin "58") (pinfunction "PD11_58") (pintype "passive"))
    )
    (net (code "94") (name "unconnected-(DD3-PE0-Pad97)") (class "Default")
      (node (ref "DD3") (pin "97") (pinfunction "PE0_97") (pintype "passive"))
    )
    (net (code "95") (name "unconnected-(DD3-PE1-Pad98)") (class "Default")
      (node (ref "DD3") (pin "98") (pinfunction "PE1_98") (pintype "passive"))
    )
    (net (code "96") (name "unconnected-(DD3-PE2-Pad1)") (class "Default")
      (node (ref "DD3") (pin "1") (pinfunction "PE2_1") (pintype "passive"))
    )
    (net (code "97") (name "unconnected-(DD3-PE3-Pad2)") (class "Default")
      (node (ref "DD3") (pin "2") (pinfunction "PE3_2") (pintype "passive"))
    )
    (net (code "98") (name "unconnected-(DD3-PE4-Pad3)") (class "Default")
      (node (ref "DD3") (pin "3") (pinfunction "PE4_3") (pintype "passive"))
    )
    (net (code "99") (name "unconnected-(DD3-PE7-Pad38)") (class "Default")
      (node (ref "DD3") (pin "38") (pinfunction "PE7_38") (pintype "passive"))
    )
    (net (code "100") (name "unconnected-(DD3-PE8-Pad39)") (class "Default")
      (node (ref "DD3") (pin "39") (pinfunction "PE8_39") (pintype "passive"))
    )
    (net (code "101") (name "unconnected-(DD3-PE10-Pad41)") (class "Default")
      (node (ref "DD3") (pin "41") (pinfunction "PE10_41") (pintype "passive"))
    )
    (net (code "102") (name "unconnected-(DD3-PE12-Pad43)") (class "Default")
      (node (ref "DD3") (pin "43") (pinfunction "PE12_43") (pintype "passive"))
    )
    (net (code "103") (name "unconnected-(DD3-PE15-Pad46)") (class "Default")
      (node (ref "DD3") (pin "46") (pinfunction "PE15_46") (pintype "passive"))
    )
    (net (code "104") (name "unconnected-(DD3-VBAT-Pad6)") (class "Default")
      (node (ref "DD3") (pin "6") (pinfunction "VBAT_6") (pintype "passive"))
    )
    (net (code "105") (name "unconnected-(DD3-VDDA-Pad22)") (class "Default")
      (node (ref "DD3") (pin "22") (pinfunction "VDDA_22") (pintype "passive"))
    )
    (net (code "106") (name "unconnected-(DD3-VREF+-Pad21)") (class "Default")
      (node (ref "DD3") (pin "21") (pinfunction "VREF+_21") (pintype "passive"))
    )
    (net (code "107") (name "unconnected-(XP1-Pad5)") (class "Default")
      (node (ref "XP1") (pin "5") (pinfunction "5_5") (pintype "passive"))
    )
    (net (code "108") (name "unconnected-(XP2-Pad5)") (class "Default")
      (node (ref "XP2") (pin "5") (pinfunction "5_5") (pintype "passive"))
    )
    (net (code "109") (name "unconnected-(XP3-Pad5)") (class "Default")
      (node (ref "XP3") (pin "5") (pinfunction "5_5") (pintype "passive"))
    )
    (net (code "110") (name "unconnected-(XP7-Pad7)") (class "Default")
      (node (ref "XP7") (pin "7") (pinfunction "7_7") (pintype "passive"))
    )
    (net (code "111") (name "unconnected-(XP7-Pad8)") (class "Default")
      (node (ref "XP7") (pin "8") (pinfunction "8_8") (pintype "passive"))
    )
    (net (code "112") (name "unconnected-(XP9-Pad5)") (class "Default")
      (node (ref "XP9") (pin "5") (pinfunction "5_5") (pintype "passive"))
    )
    (net (code "113") (name "unconnected-(XP10-Pad5)") (class "Default")
      (node (ref "XP10") (pin "5") (pinfunction "5_5") (pintype "passive"))
    )
    (net (code "114") (name "unconnected-(XP11-Pad5)") (class "Default")
      (node (ref "XP11") (pin "5") (pinfunction "5_5") (pintype "passive"))
    )
  )
)
